# pcb_v1.net
KiCad netlist of a schematic drawn in EAGLE
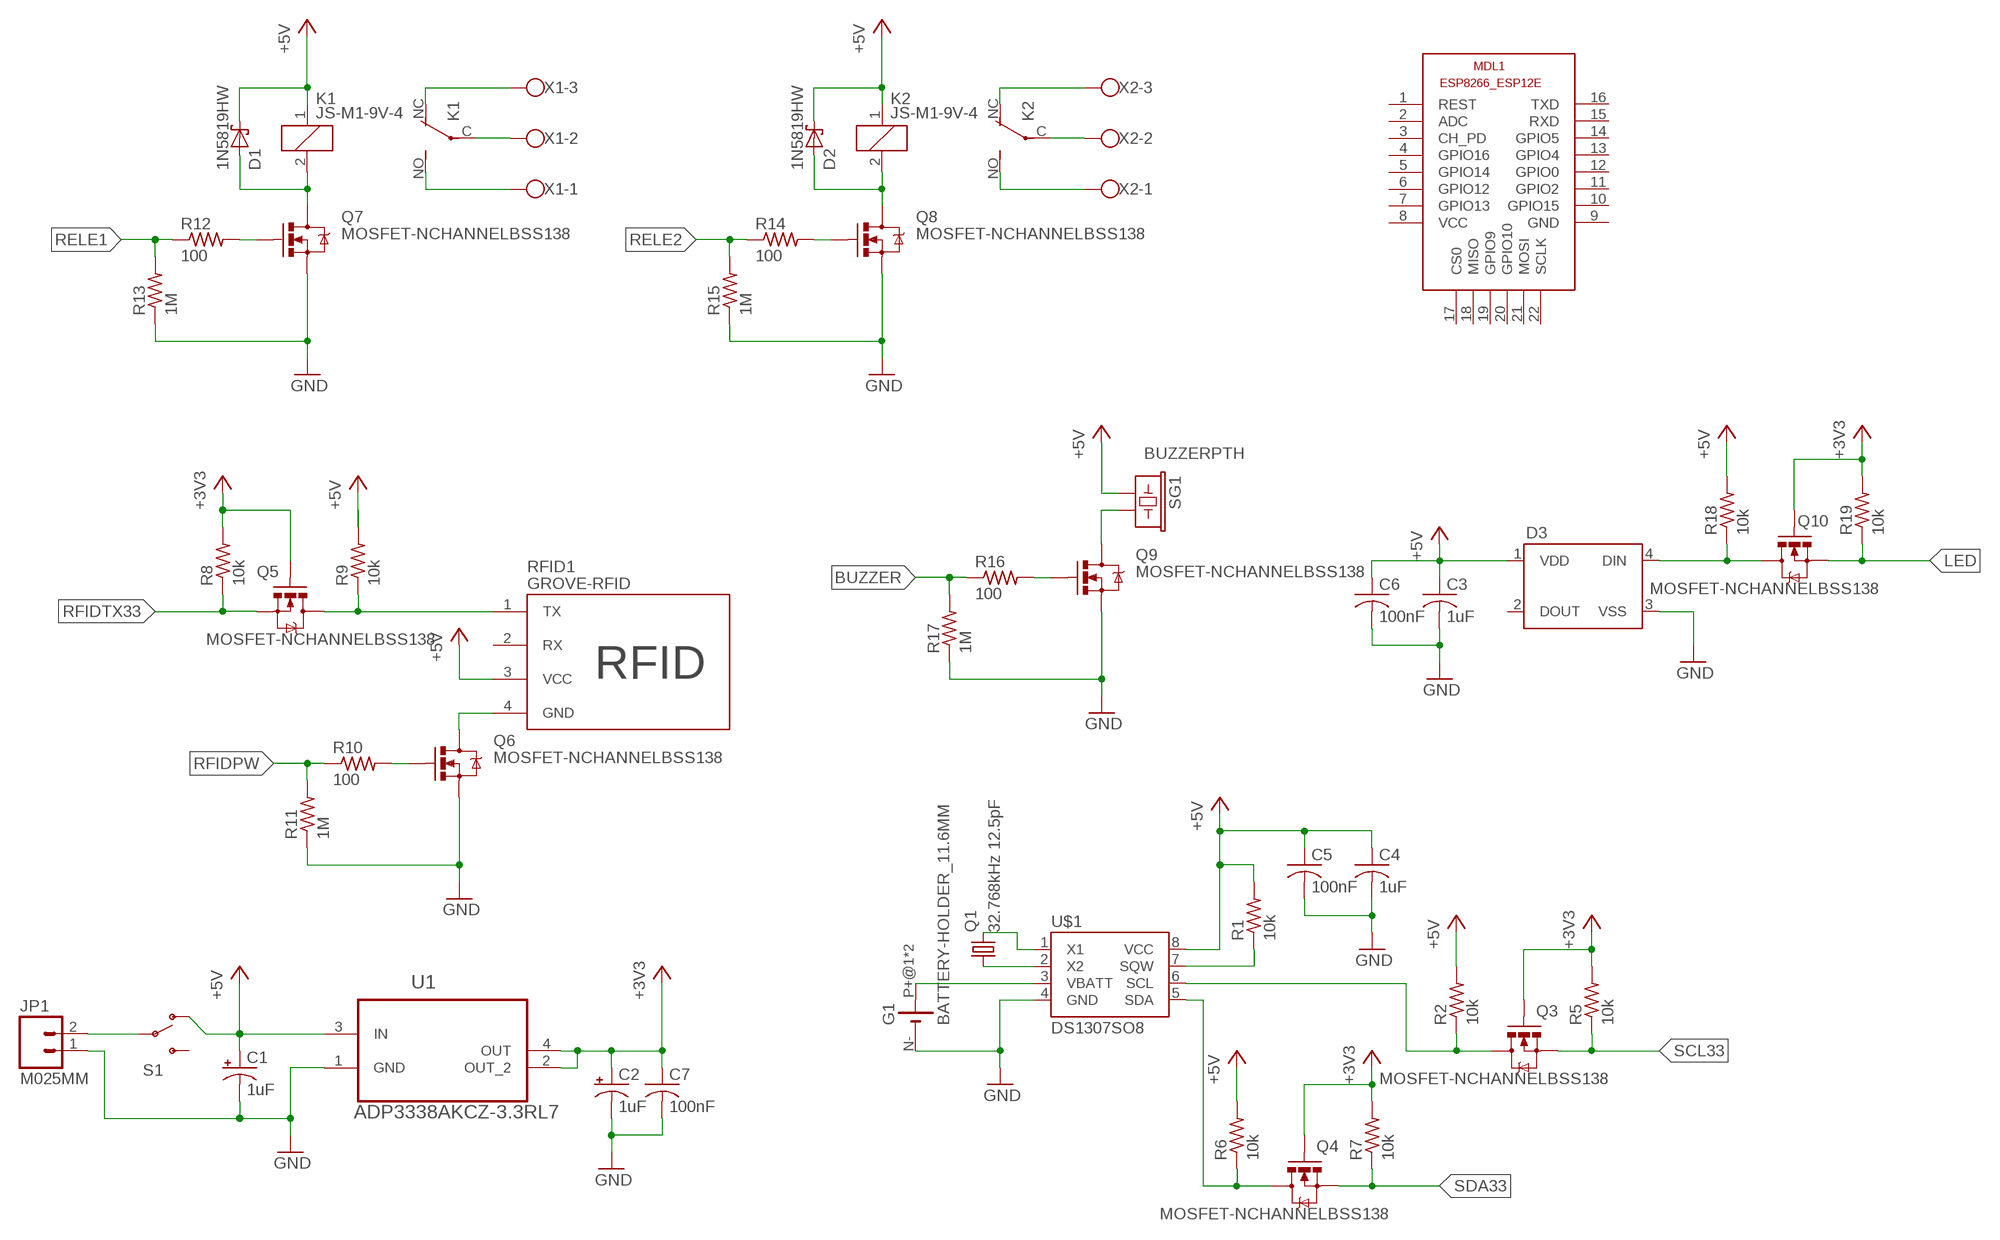
[diagram p0: schematic, sheet 1]

(export (version "E")
  (design (tool "Eeschema 10.0.6"))
  (components
    (comp (ref "C1")
      (value "1uF")
      (footprint "eagle-import:150CLZ-1010")
      (libsource (lib "eagle-import") (part "CPOL-US150CLZ-1010"))
    )
    (comp (ref "C2")
      (value "1uF")
      (footprint "eagle-import:150CLZ-1010")
      (libsource (lib "eagle-import") (part "CPOL-US150CLZ-1010"))
    )
    (comp (ref "C3")
      (value "1uF")
      (footprint "eagle-import:C0805")
      (libsource (lib "eagle-import") (part "C-USC0805"))
    )
    (comp (ref "C4")
      (value "1uF")
      (footprint "eagle-import:C0805")
      (libsource (lib "eagle-import") (part "C-USC0805"))
    )
    (comp (ref "C5")
      (value "100nF")
      (footprint "eagle-import:C0805")
      (libsource (lib "eagle-import") (part "C-USC0805"))
    )
    (comp (ref "C6")
      (value "100nF")
      (footprint "eagle-import:C0805")
      (libsource (lib "eagle-import") (part "C-USC0805"))
    )
    (comp (ref "C7")
      (value "100nF")
      (footprint "eagle-import:C0805")
      (libsource (lib "eagle-import") (part "C-USC0805"))
    )
    (comp (ref "D1")
      (value "1N5819HW")
      (footprint "eagle-import:SOD-123")
      (libsource (lib "eagle-import") (part "1N5819HW"))
    )
    (comp (ref "D2")
      (value "1N5819HW")
      (footprint "eagle-import:SOD-123")
      (libsource (lib "eagle-import") (part "1N5819HW"))
    )
    (comp (ref "D3")
      (value "WS2812B")
      (footprint "eagle-import:WS2812B")
      (libsource (lib "eagle-import") (part "WS2812B"))
    )
    (comp (ref "G1")
      (value "BATTERY-HOLDER_11.6MM")
      (footprint "eagle-import:CELL_RETAINER_11.6MM")
      (fields (field (name "MF") "KEYSTONE") (field (name "MPN") "2997"))
      (libsource (lib "eagle-import") (part "BATTERY-HOLDER_11.6MM"))
    )
    (comp (ref "JP1")
      (value "M025MM")
      (footprint "eagle-import:SCREWTERMINAL-5MM-2")
      (libsource (lib "eagle-import") (part "M025MM"))
    )
    (comp (ref "K1")
      (value "JS-M1-9V-4")
      (footprint "eagle-import:JS-M")
      (libsource (lib "eagle-import") (part "JS-M1-9V-4"))
    )
    (comp (ref "K2")
      (value "JS-M1-9V-4")
      (footprint "eagle-import:JS-M")
      (libsource (lib "eagle-import") (part "JS-M1-9V-4"))
    )
    (comp (ref "MDL1")
      (value "ESP8266-12EESP8266-ESP12E")
      (footprint "eagle-import:ESP8266-ESP12E")
      (libsource (lib "eagle-import") (part "ESP8266-12EESP8266-ESP12E"))
    )
    (comp (ref "Q1")
      (value "32.768kHz 12.5pF")
      (footprint "eagle-import:TC26H")
      (libsource (lib "eagle-import") (part "CRYSTALTC26H"))
    )
    (comp (ref "Q3")
      (value "MOSFET-NCHANNELBSS138")
      (footprint "eagle-import:SOT23-3")
      (libsource (lib "eagle-import") (part "MOSFET-NCHANNELBSS138"))
    )
    (comp (ref "Q4")
      (value "MOSFET-NCHANNELBSS138")
      (footprint "eagle-import:SOT23-3")
      (libsource (lib "eagle-import") (part "MOSFET-NCHANNELBSS138"))
    )
    (comp (ref "Q5")
      (value "MOSFET-NCHANNELBSS138")
      (footprint "eagle-import:SOT23-3")
      (libsource (lib "eagle-import") (part "MOSFET-NCHANNELBSS138"))
    )
    (comp (ref "Q6")
      (value "MOSFET-NCHANNELBSS138")
      (footprint "eagle-import:SOT23-3")
      (libsource (lib "eagle-import") (part "MOSFET-NCHANNELBSS138"))
    )
    (comp (ref "Q7")
      (value "MOSFET-NCHANNELBSS138")
      (footprint "eagle-import:SOT23-3")
      (libsource (lib "eagle-import") (part "MOSFET-NCHANNELBSS138"))
    )
    (comp (ref "Q8")
      (value "MOSFET-NCHANNELBSS138")
      (footprint "eagle-import:SOT23-3")
      (libsource (lib "eagle-import") (part "MOSFET-NCHANNELBSS138"))
    )
    (comp (ref "Q9")
      (value "MOSFET-NCHANNELBSS138")
      (footprint "eagle-import:SOT23-3")
      (libsource (lib "eagle-import") (part "MOSFET-NCHANNELBSS138"))
    )
    (comp (ref "Q10")
      (value "MOSFET-NCHANNELBSS138")
      (footprint "eagle-import:SOT23-3")
      (libsource (lib "eagle-import") (part "MOSFET-NCHANNELBSS138"))
    )
    (comp (ref "R1")
      (value "10k")
      (footprint "eagle-import:R0805")
      (libsource (lib "eagle-import") (part "R-US_R0805"))
    )
    (comp (ref "R2")
      (value "10k")
      (footprint "eagle-import:R0805")
      (libsource (lib "eagle-import") (part "R-US_R0805"))
    )
    (comp (ref "R5")
      (value "10k")
      (footprint "eagle-import:R0805")
      (libsource (lib "eagle-import") (part "R-US_R0805"))
    )
    (comp (ref "R6")
      (value "10k")
      (footprint "eagle-import:R0805")
      (libsource (lib "eagle-import") (part "R-US_R0805"))
    )
    (comp (ref "R7")
      (value "10k")
      (footprint "eagle-import:R0805")
      (libsource (lib "eagle-import") (part "R-US_R0805"))
    )
    (comp (ref "R8")
      (value "10k")
      (footprint "eagle-import:R0805")
      (libsource (lib "eagle-import") (part "R-US_R0805"))
    )
    (comp (ref "R9")
      (value "10k")
      (footprint "eagle-import:R0805")
      (libsource (lib "eagle-import") (part "R-US_R0805"))
    )
    (comp (ref "R10")
      (value "100")
      (footprint "eagle-import:R0805")
      (libsource (lib "eagle-import") (part "R-US_R0805"))
    )
    (comp (ref "R11")
      (value "1M")
      (footprint "eagle-import:R0805")
      (libsource (lib "eagle-import") (part "R-US_R0805"))
    )
    (comp (ref "R12")
      (value "100")
      (footprint "eagle-import:R0805")
      (libsource (lib "eagle-import") (part "R-US_R0805"))
    )
    (comp (ref "R13")
      (value "1M")
      (footprint "eagle-import:R0805")
      (libsource (lib "eagle-import") (part "R-US_R0805"))
    )
    (comp (ref "R14")
      (value "100")
      (footprint "eagle-import:R0805")
      (libsource (lib "eagle-import") (part "R-US_R0805"))
    )
    (comp (ref "R15")
      (value "1M")
      (footprint "eagle-import:R0805")
      (libsource (lib "eagle-import") (part "R-US_R0805"))
    )
    (comp (ref "R16")
      (value "100")
      (footprint "eagle-import:R0805")
      (libsource (lib "eagle-import") (part "R-US_R0805"))
    )
    (comp (ref "R17")
      (value "1M")
      (footprint "eagle-import:R0805")
      (libsource (lib "eagle-import") (part "R-US_R0805"))
    )
    (comp (ref "R18")
      (value "10k")
      (footprint "eagle-import:R0805")
      (libsource (lib "eagle-import") (part "R-US_R0805"))
    )
    (comp (ref "R19")
      (value "10k")
      (footprint "eagle-import:R0805")
      (libsource (lib "eagle-import") (part "R-US_R0805"))
    )
    (comp (ref "RFID1")
      (value "GROVE-RFID")
      (footprint "eagle-import:GROVE-RFID")
      (libsource (lib "eagle-import") (part "GROVE-RFID"))
    )
    (comp (ref "S1")
      (value "SWITCH-SPDTPTH")
      (footprint "eagle-import:SWITCH-SPDT")
      (libsource (lib "eagle-import") (part "SWITCH-SPDTPTH"))
    )
    (comp (ref "SG1")
      (value "BUZZERPTH")
      (footprint "eagle-import:BUZZER-12MM")
      (libsource (lib "eagle-import") (part "BUZZERPTH"))
    )
    (comp (ref "U$1")
      (value "DS1307SO8")
      (footprint "eagle-import:SO08")
      (libsource (lib "eagle-import") (part "DS1307SO8"))
    )
    (comp (ref "U1")
      (value "ADP3338AKCZ-3.3RL7")
      (footprint "eagle-import:SOT230P700X180-4N")
      (libsource (lib "eagle-import") (part "ADP3338AKCZ-3.3RL7"))
    )
    (comp (ref "X1")
      (value "W237-103")
      (footprint "eagle-import:W237-103")
      (fields (field (name "MPN") "237-103"))
      (libsource (lib "eagle-import") (part "W237-103"))
    )
    (comp (ref "X2")
      (value "W237-103")
      (footprint "eagle-import:W237-103")
      (fields (field (name "MPN") "237-103"))
      (libsource (lib "eagle-import") (part "W237-103"))
    )
  )
  (nets
    (net (code "1") (name "+3V3") (class "Default")
      (node (ref "C2") (pin "+") (pinfunction "+_+") (pintype "passive"))
      (node (ref "C7") (pin "1") (pinfunction "1_1") (pintype "passive"))
      (node (ref "Q10") (pin "1") (pinfunction "G_1") (pintype "passive"))
      (node (ref "Q3") (pin "1") (pinfunction "G_1") (pintype "passive"))
      (node (ref "Q4") (pin "1") (pinfunction "G_1") (pintype "passive"))
      (node (ref "Q5") (pin "1") (pinfunction "G_1") (pintype "passive"))
      (node (ref "R19") (pin "2") (pinfunction "2_2") (pintype "passive"))
      (node (ref "R5") (pin "2") (pinfunction "2_2") (pintype "passive"))
      (node (ref "R7") (pin "2") (pinfunction "2_2") (pintype "passive"))
      (node (ref "R8") (pin "2") (pinfunction "2_2") (pintype "passive"))
      (node (ref "U1") (pin "2") (pinfunction "OUT_2_2") (pintype "output"))
      (node (ref "U1") (pin "4") (pinfunction "OUT_4") (pintype "output"))
    )
    (net (code "2") (name "+5V") (class "Default")
      (node (ref "C1") (pin "+") (pinfunction "+_+") (pintype "passive"))
      (node (ref "C3") (pin "1") (pinfunction "1_1") (pintype "passive"))
      (node (ref "C4") (pin "1") (pinfunction "1_1") (pintype "passive"))
      (node (ref "C5") (pin "1") (pinfunction "1_1") (pintype "passive"))
      (node (ref "C6") (pin "1") (pinfunction "1_1") (pintype "passive"))
      (node (ref "D1") (pin "C") (pinfunction "C_C") (pintype "passive"))
      (node (ref "D2") (pin "C") (pinfunction "C_C") (pintype "passive"))
      (node (ref "D3") (pin "1") (pinfunction "VDD_1") (pintype "power_in"))
      (node (ref "K1") (pin "1") (pinfunction "1_1") (pintype "passive"))
      (node (ref "K2") (pin "1") (pinfunction "1_1") (pintype "passive"))
      (node (ref "R1") (pin "2") (pinfunction "2_2") (pintype "passive"))
      (node (ref "R18") (pin "2") (pinfunction "2_2") (pintype "passive"))
      (node (ref "R2") (pin "2") (pinfunction "2_2") (pintype "passive"))
      (node (ref "R6") (pin "2") (pinfunction "2_2") (pintype "passive"))
      (node (ref "R9") (pin "2") (pinfunction "2_2") (pintype "passive"))
      (node (ref "RFID1") (pin "3") (pinfunction "VCC_3") (pintype "bidirectional"))
      (node (ref "S1") (pin "1") (pinfunction "O_1") (pintype "passive"))
      (node (ref "SG1") (pin "+") (pinfunction "1_+") (pintype "passive"))
      (node (ref "U$1") (pin "8") (pinfunction "VCC_8") (pintype "bidirectional"))
      (node (ref "U1") (pin "3") (pinfunction "IN_3") (pintype "input"))
    )
    (net (code "3") (name "BUZZER") (class "Default")
      (node (ref "R16") (pin "1") (pinfunction "1_1") (pintype "passive"))
      (node (ref "R17") (pin "2") (pinfunction "2_2") (pintype "passive"))
    )
    (net (code "4") (name "GND") (class "Default")
      (node (ref "C1") (pin "-") (pinfunction "-_-") (pintype "passive"))
      (node (ref "C2") (pin "-") (pinfunction "-_-") (pintype "passive"))
      (node (ref "C3") (pin "2") (pinfunction "2_2") (pintype "passive"))
      (node (ref "C4") (pin "2") (pinfunction "2_2") (pintype "passive"))
      (node (ref "C5") (pin "2") (pinfunction "2_2") (pintype "passive"))
      (node (ref "C6") (pin "2") (pinfunction "2_2") (pintype "passive"))
      (node (ref "C7") (pin "2") (pinfunction "2_2") (pintype "passive"))
      (node (ref "D3") (pin "3") (pinfunction "VSS_3") (pintype "power_in"))
      (node (ref "G1") (pin "N-") (pinfunction "-_N-") (pintype "passive"))
      (node (ref "JP1") (pin "1") (pinfunction "1_1") (pintype "passive"))
      (node (ref "Q6") (pin "2") (pinfunction "S_2") (pintype "passive"))
      (node (ref "Q7") (pin "2") (pinfunction "S_2") (pintype "passive"))
      (node (ref "Q8") (pin "2") (pinfunction "S_2") (pintype "passive"))
      (node (ref "Q9") (pin "2") (pinfunction "S_2") (pintype "passive"))
      (node (ref "R11") (pin "1") (pinfunction "1_1") (pintype "passive"))
      (node (ref "R13") (pin "1") (pinfunction "1_1") (pintype "passive"))
      (node (ref "R15") (pin "1") (pinfunction "1_1") (pintype "passive"))
      (node (ref "R17") (pin "1") (pinfunction "1_1") (pintype "passive"))
      (node (ref "U$1") (pin "4") (pinfunction "GND_4") (pintype "bidirectional"))
      (node (ref "U1") (pin "1") (pinfunction "GND_1") (pintype "passive"))
    )
    (net (code "5") (name "LED") (class "Default")
      (node (ref "Q10") (pin "2") (pinfunction "S_2") (pintype "passive"))
      (node (ref "R19") (pin "1") (pinfunction "1_1") (pintype "passive"))
    )
    (net (code "6") (name "Net-(D3-DIN)") (class "Default")
      (node (ref "D3") (pin "4") (pinfunction "DIN_4") (pintype "input"))
      (node (ref "Q10") (pin "3") (pinfunction "D_3") (pintype "passive"))
      (node (ref "R18") (pin "1") (pinfunction "1_1") (pintype "passive"))
    )
    (net (code "7") (name "Net-(K1B-O)") (class "Default")
      (node (ref "K1") (pin "NC") (pinfunction "O_NC") (pintype "passive"))
      (node (ref "X1") (pin "3") (pinfunction "KL_3") (pintype "passive"))
    )
    (net (code "8") (name "Net-(K1B-P)") (class "Default")
      (node (ref "K1") (pin "C") (pinfunction "P_C") (pintype "passive"))
      (node (ref "X1") (pin "2") (pinfunction "KL_2") (pintype "passive"))
    )
    (net (code "9") (name "Net-(K1B-S)") (class "Default")
      (node (ref "K1") (pin "NO") (pinfunction "S_NO") (pintype "passive"))
      (node (ref "X1") (pin "1") (pinfunction "KL_1") (pintype "passive"))
    )
    (net (code "10") (name "Net-(K2B-O)") (class "Default")
      (node (ref "K2") (pin "NC") (pinfunction "O_NC") (pintype "passive"))
      (node (ref "X2") (pin "3") (pinfunction "KL_3") (pintype "passive"))
    )
    (net (code "11") (name "Net-(K2B-P)") (class "Default")
      (node (ref "K2") (pin "C") (pinfunction "P_C") (pintype "passive"))
      (node (ref "X2") (pin "2") (pinfunction "KL_2") (pintype "passive"))
    )
    (net (code "12") (name "Net-(K2B-S)") (class "Default")
      (node (ref "K2") (pin "NO") (pinfunction "S_NO") (pintype "passive"))
      (node (ref "X2") (pin "1") (pinfunction "KL_1") (pintype "passive"))
    )
    (net (code "13") (name "Net-(Q3-D)") (class "Default")
      (node (ref "Q3") (pin "3") (pinfunction "D_3") (pintype "passive"))
      (node (ref "R2") (pin "1") (pinfunction "1_1") (pintype "passive"))
      (node (ref "U$1") (pin "6") (pinfunction "SCL_6") (pintype "bidirectional"))
    )
    (net (code "14") (name "Net-(Q4-D)") (class "Default")
      (node (ref "Q4") (pin "3") (pinfunction "D_3") (pintype "passive"))
      (node (ref "R6") (pin "1") (pinfunction "1_1") (pintype "passive"))
      (node (ref "U$1") (pin "5") (pinfunction "SDA_5") (pintype "bidirectional"))
    )
    (net (code "15") (name "Net-(Q5-D)") (class "Default")
      (node (ref "Q5") (pin "3") (pinfunction "D_3") (pintype "passive"))
      (node (ref "R9") (pin "1") (pinfunction "1_1") (pintype "passive"))
      (node (ref "RFID1") (pin "1") (pinfunction "TX_1") (pintype "bidirectional"))
    )
    (net (code "16") (name "Net-(Q6-D)") (class "Default")
      (node (ref "Q6") (pin "3") (pinfunction "D_3") (pintype "passive"))
      (node (ref "RFID1") (pin "4") (pinfunction "GND_4") (pintype "bidirectional"))
    )
    (net (code "17") (name "Net-(Q6-G)") (class "Default")
      (node (ref "Q6") (pin "1") (pinfunction "G_1") (pintype "passive"))
      (node (ref "R10") (pin "2") (pinfunction "2_2") (pintype "passive"))
    )
    (net (code "18") (name "Net-(Q7-D)") (class "Default")
      (node (ref "D1") (pin "A") (pinfunction "A_A") (pintype "passive"))
      (node (ref "K1") (pin "2") (pinfunction "2_2") (pintype "passive"))
      (node (ref "Q7") (pin "3") (pinfunction "D_3") (pintype "passive"))
    )
    (net (code "19") (name "Net-(Q7-G)") (class "Default")
      (node (ref "Q7") (pin "1") (pinfunction "G_1") (pintype "passive"))
      (node (ref "R12") (pin "2") (pinfunction "2_2") (pintype "passive"))
    )
    (net (code "20") (name "Net-(Q8-D)") (class "Default")
      (node (ref "D2") (pin "A") (pinfunction "A_A") (pintype "passive"))
      (node (ref "K2") (pin "2") (pinfunction "2_2") (pintype "passive"))
      (node (ref "Q8") (pin "3") (pinfunction "D_3") (pintype "passive"))
    )
    (net (code "21") (name "Net-(Q8-G)") (class "Default")
      (node (ref "Q8") (pin "1") (pinfunction "G_1") (pintype "passive"))
      (node (ref "R14") (pin "2") (pinfunction "2_2") (pintype "passive"))
    )
    (net (code "22") (name "Net-(Q9-D)") (class "Default")
      (node (ref "Q9") (pin "3") (pinfunction "D_3") (pintype "passive"))
      (node (ref "SG1") (pin "-") (pinfunction "2_-") (pintype "passive"))
    )
    (net (code "23") (name "Net-(Q9-G)") (class "Default")
      (node (ref "Q9") (pin "1") (pinfunction "G_1") (pintype "passive"))
      (node (ref "R16") (pin "2") (pinfunction "2_2") (pintype "passive"))
    )
    (net (code "24") (name "Net-(S1-P)") (class "Default")
      (node (ref "JP1") (pin "2") (pinfunction "2_2") (pintype "passive"))
      (node (ref "S1") (pin "2") (pinfunction "P_2") (pintype "passive"))
    )
    (net (code "25") (name "Net-(U$1-SQW)") (class "Default")
      (node (ref "R1") (pin "1") (pinfunction "1_1") (pintype "passive"))
      (node (ref "U$1") (pin "7") (pinfunction "SQW_7") (pintype "bidirectional"))
    )
    (net (code "26") (name "Net-(U$1-VBATT)") (class "Default")
      (node (ref "G1") (pin "P+@1") (pinfunction "+_P+@1") (pintype "passive"))
      (node (ref "G1") (pin "P+@2") (pinfunction "+_P+@2") (pintype "passive"))
      (node (ref "U$1") (pin "3") (pinfunction "VBATT_3") (pintype "bidirectional"))
    )
    (net (code "27") (name "Net-(U$1-X1)") (class "Default")
      (node (ref "Q1") (pin "2") (pinfunction "2_2") (pintype "passive"))
      (node (ref "U$1") (pin "1") (pinfunction "X1_1") (pintype "bidirectional"))
    )
    (net (code "28") (name "Net-(U$1-X2)") (class "Default")
      (node (ref "Q1") (pin "1") (pinfunction "1_1") (pintype "passive"))
      (node (ref "U$1") (pin "2") (pinfunction "X2_2") (pintype "bidirectional"))
    )
    (net (code "29") (name "RELE1") (class "Default")
      (node (ref "R12") (pin "1") (pinfunction "1_1") (pintype "passive"))
      (node (ref "R13") (pin "2") (pinfunction "2_2") (pintype "passive"))
    )
    (net (code "30") (name "RELE2") (class "Default")
      (node (ref "R14") (pin "1") (pinfunction "1_1") (pintype "passive"))
      (node (ref "R15") (pin "2") (pinfunction "2_2") (pintype "passive"))
    )
    (net (code "31") (name "RFIDPW") (class "Default")
      (node (ref "R10") (pin "1") (pinfunction "1_1") (pintype "passive"))
      (node (ref "R11") (pin "2") (pinfunction "2_2") (pintype "passive"))
    )
    (net (code "32") (name "RFIDTX33") (class "Default")
      (node (ref "Q5") (pin "2") (pinfunction "S_2") (pintype "passive"))
      (node (ref "R8") (pin "1") (pinfunction "1_1") (pintype "passive"))
    )
    (net (code "33") (name "SCL33") (class "Default")
      (node (ref "Q3") (pin "2") (pinfunction "S_2") (pintype "passive"))
      (node (ref "R5") (pin "1") (pinfunction "1_1") (pintype "passive"))
    )
    (net (code "34") (name "SDA33") (class "Default")
      (node (ref "Q4") (pin "2") (pinfunction "S_2") (pintype "passive"))
      (node (ref "R7") (pin "1") (pinfunction "1_1") (pintype "passive"))
    )
    (net (code "35") (name "unconnected-(D3-DOUT-Pad2)") (class "Default")
      (node (ref "D3") (pin "2") (pinfunction "DOUT_2") (pintype "output"))
    )
    (net (code "36") (name "unconnected-(MDL1-ADC-Pad2)") (class "Default")
      (node (ref "MDL1") (pin "2") (pinfunction "ADC_2") (pintype "bidirectional"))
    )
    (net (code "37") (name "unconnected-(MDL1-CH_PD-Pad3)") (class "Default")
      (node (ref "MDL1") (pin "3") (pinfunction "CH_PD_3") (pintype "bidirectional"))
    )
    (net (code "38") (name "unconnected-(MDL1-CS0-Pad17)") (class "Default")
      (node (ref "MDL1") (pin "17") (pinfunction "CS0_17") (pintype "bidirectional"))
    )
    (net (code "39") (name "unconnected-(MDL1-GND-Pad9)") (class "Default")
      (node (ref "MDL1") (pin "9") (pinfunction "GND_9") (pintype "bidirectional"))
    )
    (net (code "40") (name "unconnected-(MDL1-GPIO0-Pad12)") (class "Default")
      (node (ref "MDL1") (pin "12") (pinfunction "GPIO0_12") (pintype "bidirectional"))
    )
    (net (code "41") (name "unconnected-(MDL1-GPIO2-Pad11)") (class "Default")
      (node (ref "MDL1") (pin "11") (pinfunction "GPIO2_11") (pintype "bidirectional"))
    )
    (net (code "42") (name "unconnected-(MDL1-GPIO4-Pad13)") (class "Default")
      (node (ref "MDL1") (pin "13") (pinfunction "GPIO4_13") (pintype "bidirectional"))
    )
    (net (code "43") (name "unconnected-(MDL1-GPIO5-Pad14)") (class "Default")
      (node (ref "MDL1") (pin "14") (pinfunction "GPIO5_14") (pintype "bidirectional"))
    )
    (net (code "44") (name "unconnected-(MDL1-GPIO9-Pad19)") (class "Default")
      (node (ref "MDL1") (pin "19") (pinfunction "GPIO9_19") (pintype "bidirectional"))
    )
    (net (code "45") (name "unconnected-(MDL1-GPIO10-Pad20)") (class "Default")
      (node (ref "MDL1") (pin "20") (pinfunction "GPIO10_20") (pintype "bidirectional"))
    )
    (net (code "46") (name "unconnected-(MDL1-GPIO12-Pad6)") (class "Default")
      (node (ref "MDL1") (pin "6") (pinfunction "GPIO12_6") (pintype "bidirectional"))
    )
    (net (code "47") (name "unconnected-(MDL1-GPIO13-Pad7)") (class "Default")
      (node (ref "MDL1") (pin "7") (pinfunction "GPIO13_7") (pintype "bidirectional"))
    )
    (net (code "48") (name "unconnected-(MDL1-GPIO14-Pad5)") (class "Default")
      (node (ref "MDL1") (pin "5") (pinfunction "GPIO14_5") (pintype "bidirectional"))
    )
    (net (code "49") (name "unconnected-(MDL1-GPIO15-Pad10)") (class "Default")
      (node (ref "MDL1") (pin "10") (pinfunction "GPIO15_10") (pintype "bidirectional"))
    )
    (net (code "50") (name "unconnected-(MDL1-GPIO16-Pad4)") (class "Default")
      (node (ref "MDL1") (pin "4") (pinfunction "GPIO16_4") (pintype "bidirectional"))
    )
    (net (code "51") (name "unconnected-(MDL1-MISO-Pad18)") (class "Default")
      (node (ref "MDL1") (pin "18") (pinfunction "MISO_18") (pintype "bidirectional"))
    )
    (net (code "52") (name "unconnected-(MDL1-MOSI-Pad21)") (class "Default")
      (node (ref "MDL1") (pin "21") (pinfunction "MOSI_21") (pintype "bidirectional"))
    )
    (net (code "53") (name "unconnected-(MDL1-REST-Pad1)") (class "Default")
      (node (ref "MDL1") (pin "1") (pinfunction "REST_1") (pintype "bidirectional"))
    )
    (net (code "54") (name "unconnected-(MDL1-RXD-Pad15)") (class "Default")
      (node (ref "MDL1") (pin "15") (pinfunction "RXD_15") (pintype "bidirectional"))
    )
    (net (code "55") (name "unconnected-(MDL1-SCLK-Pad22)") (class "Default")
      (node (ref "MDL1") (pin "22") (pinfunction "SCLK_22") (pintype "bidirectional"))
    )
    (net (code "56") (name "unconnected-(MDL1-TXD-Pad16)") (class "Default")
      (node (ref "MDL1") (pin "16") (pinfunction "TXD_16") (pintype "bidirectional"))
    )
    (net (code "57") (name "unconnected-(MDL1-VCC-Pad8)") (class "Default")
      (node (ref "MDL1") (pin "8") (pinfunction "VCC_8") (pintype "bidirectional"))
    )
    (net (code "58") (name "unconnected-(RFID1-RX-Pad2)") (class "Default")
      (node (ref "RFID1") (pin "2") (pinfunction "RX_2") (pintype "bidirectional"))
    )
    (net (code "59") (name "unconnected-(S1-S-Pad3)") (class "Default")
      (node (ref "S1") (pin "3") (pinfunction "S_3") (pintype "passive"))
    )
  )
)
